# adc.net
KiCad netlist of a schematic drawn in EAGLE
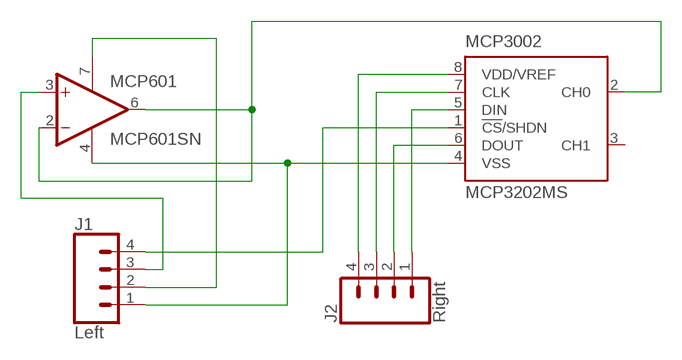
[diagram p0: schematic, sheet 1]

(export (version "E")
  (design (tool "Eeschema 10.0.6"))
  (components
    (comp (ref "J1")
      (value "Left")
      (footprint "eagle-import:1X04")
      (libsource (lib "eagle-import") (part "CONN_04"))
    )
    (comp (ref "J2")
      (value "Right")
      (footprint "eagle-import:1X04")
      (libsource (lib "eagle-import") (part "CONN_04"))
    )
    (comp (ref "MCP601")
      (value "MCP601SN")
      (footprint "eagle-import:SO08")
      (libsource (lib "eagle-import") (part "MCP601SN"))
    )
    (comp (ref "MCP3002")
      (value "MCP3202MS")
      (footprint "eagle-import:MSOP8")
      (fields (field (name "MF") "MICROCHIP") (field (name "MPN") "MCP3202-CI/MS"))
      (libsource (lib "eagle-import") (part "MCP3202MS"))
    )
  )
  (nets
    (net (code "1") (name "Net-(MCP601-+IN)") (class "Default")
      (node (ref "J1") (pin "3") (pinfunction "3_3") (pintype "passive"))
      (node (ref "MCP601") (pin "3") (pinfunction "+IN_3") (pintype "input"))
    )
    (net (code "2") (name "Net-(MCP601-V+)") (class "Default")
      (node (ref "J1") (pin "2") (pinfunction "2_2") (pintype "passive"))
      (node (ref "MCP601") (pin "7") (pinfunction "V+_7") (pintype "power_in"))
    )
    (net (code "3") (name "Net-(MCP3002-CH0)") (class "Default")
      (node (ref "MCP3002") (pin "2") (pinfunction "CH0_2") (pintype "input"))
      (node (ref "MCP601") (pin "2") (pinfunction "-IN_2") (pintype "input"))
      (node (ref "MCP601") (pin "6") (pinfunction "OUT_6") (pintype "output"))
    )
    (net (code "4") (name "Net-(MCP3002-CLK)") (class "Default")
      (node (ref "J2") (pin "3") (pinfunction "3_3") (pintype "passive"))
      (node (ref "MCP3002") (pin "7") (pinfunction "CLK_7") (pintype "input"))
    )
    (net (code "5") (name "Net-(MCP3002-DIN)") (class "Default")
      (node (ref "J2") (pin "1") (pinfunction "1_1") (pintype "passive"))
      (node (ref "MCP3002") (pin "5") (pinfunction "DIN_5") (pintype "input"))
    )
    (net (code "6") (name "Net-(MCP3002-DOUT)") (class "Default")
      (node (ref "J2") (pin "2") (pinfunction "2_2") (pintype "passive"))
      (node (ref "MCP3002") (pin "6") (pinfunction "DOUT_6") (pintype "input"))
    )
    (net (code "7") (name "Net-(MCP3002-VDD{slash}VREF)") (class "Default")
      (node (ref "J2") (pin "4") (pinfunction "4_4") (pintype "passive"))
      (node (ref "MCP3002") (pin "8") (pinfunction "VDD/VREF_8") (pintype "input"))
    )
    (net (code "8") (name "Net-(MCP3002-VSS)") (class "Default")
      (node (ref "J1") (pin "1") (pinfunction "1_1") (pintype "passive"))
      (node (ref "MCP3002") (pin "4") (pinfunction "VSS_4") (pintype "input"))
      (node (ref "MCP601") (pin "4") (pinfunction "V-_4") (pintype "power_in"))
    )
    (net (code "9") (name "Net-(MCP3002-~{CS}{slash}SHDN)") (class "Default")
      (node (ref "J1") (pin "4") (pinfunction "4_4") (pintype "passive"))
      (node (ref "MCP3002") (pin "1") (pinfunction "~{CS}/SHDN_1") (pintype "input"))
    )
    (net (code "10") (name "unconnected-(MCP3002-CH1-Pad3)") (class "Default")
      (node (ref "MCP3002") (pin "3") (pinfunction "CH1_3") (pintype "input"))
    )
  )
)
